# DualDriver.net
KiCad netlist of a schematic drawn in Altium Designer
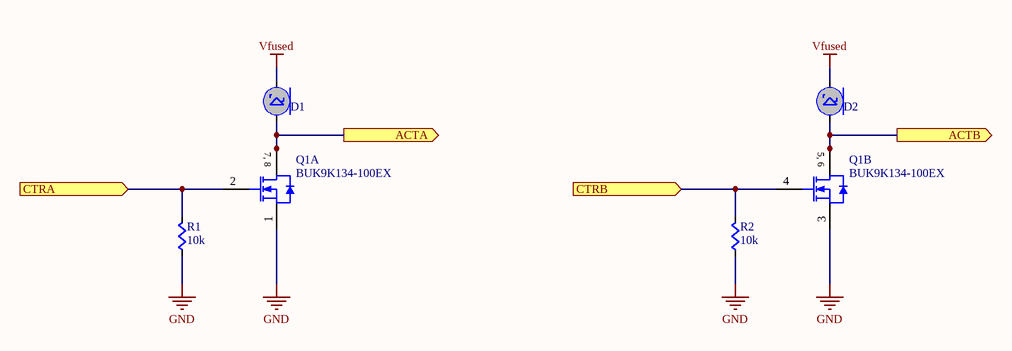
[diagram p0: DualDriver.SchDoc]

(export (version "E")
  (design (tool "Eeschema 10.0.6"))
  (components
    (comp (ref "D1")
      (value "Schottky")
      (footprint "SS110-TP")
      (description "Schottky Diode Template")
      (libsource (lib "Semiconductors") (part "Schottky"))
    )
    (comp (ref "D2")
      (value "Schottky")
      (footprint "SS110-TP")
      (description "Schottky Diode Template")
      (libsource (lib "Semiconductors") (part "Schottky"))
    )
    (comp (ref "Q1")
      (value "BUK9K134-100EX")
      (footprint "NXP_SOT1205")
      (description "MOSFET DUAL N-CH 100V 8.5A SOT1205")
      (libsource (lib "Semiconductors") (part "BUK9K134-100EX"))
    )
    (comp (ref "R1")
      (value "10k")
      (footprint "RES0603")
      (fields (field (name "Comment") "Res"))
      (libsource (lib "Passives") (part "Res"))
    )
    (comp (ref "R2")
      (value "10k")
      (footprint "RES0603")
      (fields (field (name "Comment") "Res"))
      (libsource (lib "Passives") (part "Res"))
    )
  )
  (nets
    (net (code "1") (name "/ACTA") (class "Default")
      (node (ref "D1") (pin "A") (pinfunction "A_A") (pintype "passive"))
      (node (ref "Q1") (pin "7") (pinfunction "D_7") (pintype "passive"))
      (node (ref "Q1") (pin "8") (pinfunction "D_8") (pintype "passive"))
    )
    (net (code "2") (name "/ACTB") (class "Default")
      (node (ref "D2") (pin "A") (pinfunction "A_A") (pintype "passive"))
      (node (ref "Q1") (pin "5") (pinfunction "D_5") (pintype "passive"))
      (node (ref "Q1") (pin "6") (pinfunction "D_6") (pintype "passive"))
    )
    (net (code "3") (name "/CTRA") (class "Default")
      (node (ref "Q1") (pin "2") (pinfunction "G_2") (pintype "passive"))
      (node (ref "R1") (pin "1") (pinfunction "A_1") (pintype "passive"))
    )
    (net (code "4") (name "/CTRB") (class "Default")
      (node (ref "Q1") (pin "4") (pinfunction "G_4") (pintype "passive"))
      (node (ref "R2") (pin "1") (pinfunction "A_1") (pintype "passive"))
    )
    (net (code "5") (name "GND") (class "Default")
      (node (ref "Q1") (pin "1") (pinfunction "S_1") (pintype "passive"))
      (node (ref "Q1") (pin "3") (pinfunction "S_3") (pintype "passive"))
      (node (ref "R1") (pin "2") (pinfunction "B_2") (pintype "passive"))
      (node (ref "R2") (pin "2") (pinfunction "B_2") (pintype "passive"))
    )
    (net (code "6") (name "Vfused") (class "Default")
      (node (ref "D1") (pin "C") (pinfunction "C_C") (pintype "passive"))
      (node (ref "D2") (pin "C") (pinfunction "C_C") (pintype "passive"))
    )
  )
)
